# 05-USB-UART.net
KiCad netlist of a schematic drawn in Altium Designer
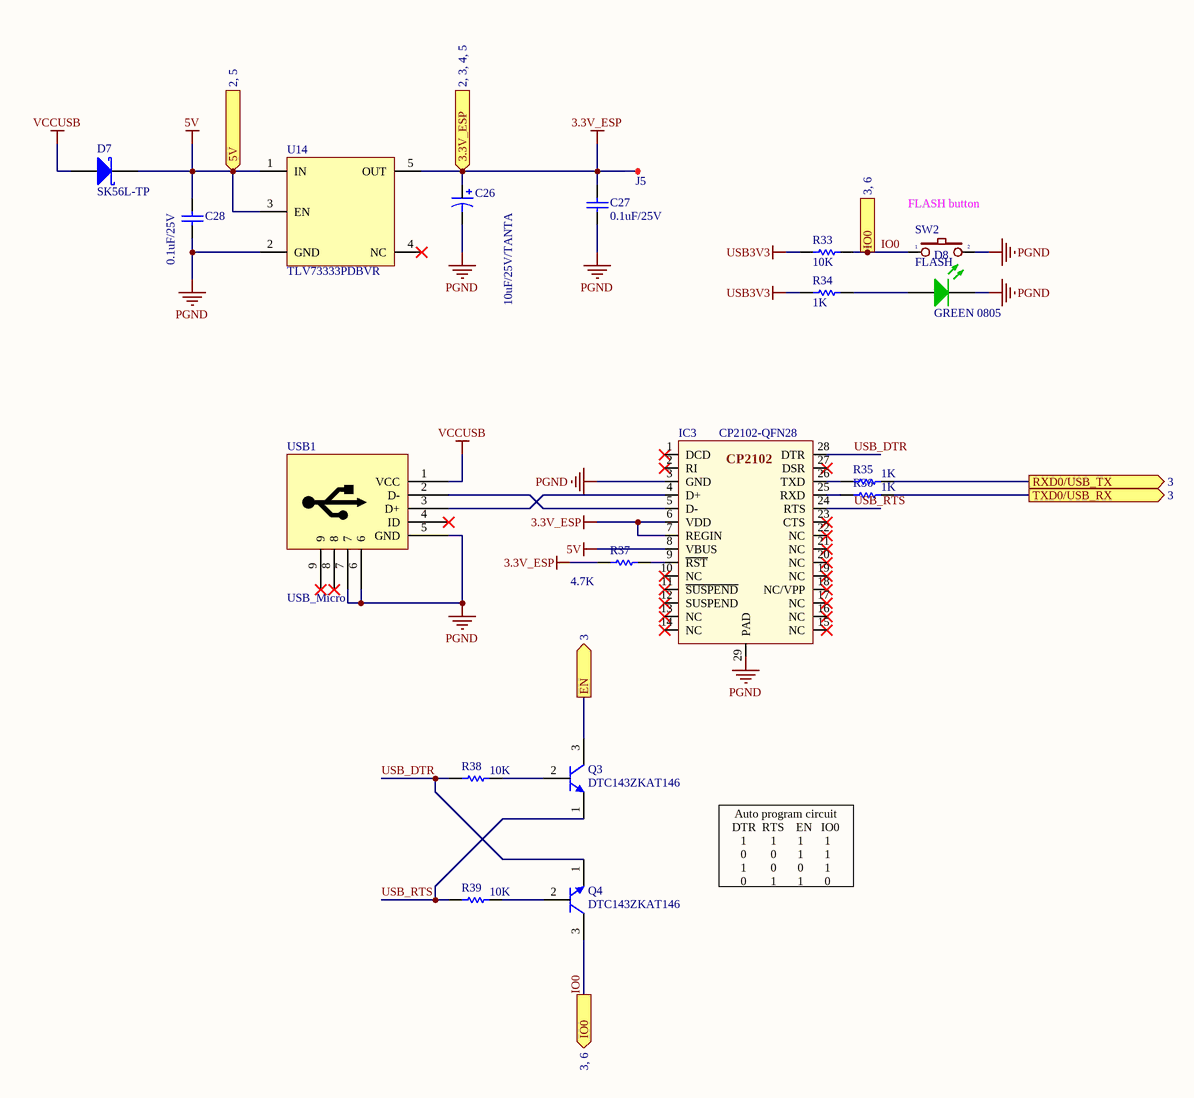
[diagram p0: 05-USB-UART.SchDoc]

(export (version "E")
  (design (tool "Eeschema 10.0.6"))
  (components
    (comp (ref "C26")
      (value "10uF/25V/TANTA")
      (footprint "CAP TANT CASE B SMD")
      (description "10µF Molded Tantalum Capacitors 25V 1411 (3528 Metric) 3 Ohm")
      (fields (field (name "MANUFACTURER") "KEMET"))
      (libsource (lib "GSHT_181013") (part "TAJB106M025RNJ"))
    )
    (comp (ref "C27")
      (value "0.1uF/25V")
      (footprint "CAP_CERA_C2012(CC0805INCH)")
      (description "0.1µF ±10% 25V Ceramic Capacitor X7R 0805 (2012 Metric)")
      (fields (field (name "MANUFACTURER") "KEMET"))
      (libsource (lib "GSHT_181013") (part "0.1uF/50V/C0603/10%"))
    )
    (comp (ref "C28")
      (value "0.1uF/25V")
      (footprint "CAP_CERA_C2012(CC0805INCH)")
      (description "0.1µF ±10% 25V Ceramic Capacitor X7R 0805 (2012 Metric)")
      (libsource (lib "GSHT_181013") (part "0.1uF/50V/C0603/10%"))
    )
    (comp (ref "D7")
      (value "SK56L-TP")
      (footprint "30# SK56L-TPMSCT-ND")
      (description "DIODE SCHOTTKY 60V 5A DO214AB")
      (libsource (lib "GSHT_181013") (part "30# SK56L-TP"))
    )
    (comp (ref "D8")
      (value "GREEN 0805")
      (footprint "Led 0805G")
      (description "Green 571nm LED Indication - Discrete 2V 0805 (2012 Metric)")
      (libsource (lib "GSHT_181013") (part "LED GREEN 0603"))
    )
    (comp (ref "IC3")
      (value "CP2102-QFN28")
      (footprint "CP2102-QFN28")
      (description "USB Bridge, USB to UART USB 2.0 UART Interface 28-QFN (5x5)")
      (libsource (lib "lpson") (part "CP2102"))
    )
    (comp (ref "J5")
      (value "TEST POINT")
      (footprint "TEST POINT 1mm")
      (description "TPoint")
      (libsource (lib "GSHT_181013") (part "PAD 1mm"))
    )
    (comp (ref "Q3")
      (value "DTC143ZKAT146")
      (footprint "6# DTC143ZKAT146-E")
      (description "Pre-Biased Bipolar Transistor (BJT) NPN - Pre-Biased 50V 100mA 250MHz 200mW Surface Mount SMT3")
      (libsource (lib "GSHT_181013") (part "6#DTC143ZKAT146"))
    )
    (comp (ref "Q4")
      (value "DTC143ZKAT146")
      (footprint "6# DTC143ZKAT146-E")
      (description "Pre-Biased Bipolar Transistor (BJT) NPN - Pre-Biased 50V 100mA 250MHz 200mW Surface Mount SMT3")
      (libsource (lib "GSHT_181013") (part "6#DTC143ZKAT146"))
    )
    (comp (ref "R33")
      (value "10K")
      (footprint "Res 0805 SMD")
      (description "10 kOhms ±1% 0.125W, 1/8W Chip Resistor 0805 (2012 Metric) Thick Film")
      (libsource (lib "GSHT_181013") (part "200K/R0603/1%"))
    )
    (comp (ref "R34")
      (value "1K")
      (footprint "Res 0805 SMD")
      (description "1 kOhms ±1% 0.125W, 1/8W Chip Resistor 0805 (2012 Metric) Automotive AEC-Q200 Thick Film")
      (libsource (lib "GSHT_181013") (part "200K/R0603/1%"))
    )
    (comp (ref "R35")
      (value "1K")
      (footprint "Res 0805 SMD")
      (description "1 kOhms ±1% 0.125W, 1/8W Chip Resistor 0805 (2012 Metric) Automotive AEC-Q200 Thick Film")
      (libsource (lib "GSHT_181013") (part "34.8K/R0805/1%"))
    )
    (comp (ref "R36")
      (value "1K")
      (footprint "Res 0805 SMD")
      (description "1 kOhms ±1% 0.125W, 1/8W Chip Resistor 0805 (2012 Metric) Automotive AEC-Q200 Thick Film")
      (libsource (lib "GSHT_181013") (part "34.8K/R0805/1%"))
    )
    (comp (ref "R37")
      (value "4.7K")
      (footprint "Res 0805 SMD")
      (description "4.7 kOhms ±1% 0.125W, 1/8W Chip Resistor 0805 (2012 Metric) Thick Film")
      (libsource (lib "GSHT_181013") (part "34.8K/R0805/1%"))
    )
    (comp (ref "R38")
      (value "10K")
      (footprint "Res 0805 SMD")
      (description "10 kOhms ±1% 0.125W, 1/8W Chip Resistor 0805 (2012 Metric) Thick Film")
      (libsource (lib "GSHT_181013") (part "34.8K/R0805/1%"))
    )
    (comp (ref "R39")
      (value "10K")
      (footprint "Res 0805 SMD")
      (description "10 kOhms ±1% 0.125W, 1/8W Chip Resistor 0805 (2012 Metric) Thick Film")
      (libsource (lib "GSHT_181013") (part "34.8K/R0805/1%"))
    )
    (comp (ref "SW2")
      (value "FLASH")
      (footprint "Button 3x4mm")
      (description "SWITCH TACTILE SPST-NO 0.05A 12V")
      (libsource (lib "lpson") (part "SW2"))
    )
    (comp (ref "U14")
      (value "TLV73333PDBVR")
      (footprint "20# TLV73333PDBVR")
      (description "Linear Voltage Regulator IC Positive Fixed 1 Output 3.3V 300mA SOT-23-5")
      (libsource (lib "GSHT_181013") (part "20#TLV73333PDBVR"))
    )
    (comp (ref "USB1")
      (value "USB_Micro")
      (footprint "USB_MICRO_B - Digikey")
      (description "USB - micro B USB 2.0 Receptacle Connector 5 Position Surface Mount, Right Angle; Through Hole")
      (libsource (lib "lpson") (part "USB_MINI"))
    )
  )
  (nets
    (net (code "1") (name "/EN") (class "Default")
      (node (ref "Q3") (pin "3") (pinfunction "C_3") (pintype "passive"))
    )
    (net (code "2") (name "/IO0") (class "Default")
      (node (ref "Q4") (pin "3") (pinfunction "C_3") (pintype "passive"))
      (node (ref "R33") (pin "2") (pinfunction "2_2") (pintype "passive"))
      (node (ref "SW2") (pin "1") (pinfunction "1_1") (pintype "passive"))
    )
    (net (code "3") (name "/RXD0{slash}USB_TX") (class "Default")
      (node (ref "R35") (pin "1") (pinfunction "1_1") (pintype "passive"))
    )
    (net (code "4") (name "/TXD0{slash}USB_RX") (class "Default")
      (node (ref "R36") (pin "1") (pinfunction "1_1") (pintype "passive"))
    )
    (net (code "5") (name "/USB_DTR") (class "Default")
      (node (ref "IC3") (pin "28") (pinfunction "DTR_28") (pintype "passive"))
      (node (ref "Q4") (pin "1") (pinfunction "E_1") (pintype "passive"))
      (node (ref "R38") (pin "2") (pinfunction "2_2") (pintype "passive"))
    )
    (net (code "6") (name "/USB_RTS") (class "Default")
      (node (ref "IC3") (pin "24") (pinfunction "RTS_24") (pintype "passive"))
      (node (ref "Q3") (pin "1") (pinfunction "E_1") (pintype "passive"))
      (node (ref "R39") (pin "2") (pinfunction "2_2") (pintype "passive"))
    )
    (net (code "7") (name "3.3V_ESP") (class "Default")
      (node (ref "C26") (pin "1") (pinfunction "1_1") (pintype "passive"))
      (node (ref "C27") (pin "2") (pinfunction "2_2") (pintype "passive"))
      (node (ref "IC3") (pin "6") (pinfunction "VDD_6") (pintype "passive"))
      (node (ref "IC3") (pin "7") (pinfunction "REGIN_7") (pintype "passive"))
      (node (ref "J5") (pin "1") (pinfunction "TP_1") (pintype "passive"))
      (node (ref "R37") (pin "1") (pinfunction "1_1") (pintype "passive"))
      (node (ref "U14") (pin "5") (pinfunction "OUT_5") (pintype "passive"))
    )
    (net (code "8") (name "5V") (class "Default")
      (node (ref "C28") (pin "2") (pinfunction "2_2") (pintype "passive"))
      (node (ref "D7") (pin "2") (pinfunction "K_2") (pintype "passive"))
      (node (ref "IC3") (pin "8") (pinfunction "VBUS_8") (pintype "passive"))
      (node (ref "U14") (pin "1") (pinfunction "IN_1") (pintype "passive"))
      (node (ref "U14") (pin "3") (pinfunction "EN_3") (pintype "passive"))
    )
    (net (code "9") (name "Net-(D8-A)") (class "Default")
      (node (ref "D8") (pin "1") (pinfunction "A_1") (pintype "passive"))
      (node (ref "R34") (pin "2") (pinfunction "2_2") (pintype "passive"))
    )
    (net (code "10") (name "Net-(IC3-D+)") (class "Default")
      (node (ref "IC3") (pin "4") (pinfunction "D+_4") (pintype "passive"))
      (node (ref "USB1") (pin "3") (pinfunction "D+_3") (pintype "passive"))
    )
    (net (code "11") (name "Net-(IC3-D-)") (class "Default")
      (node (ref "IC3") (pin "5") (pinfunction "D-_5") (pintype "passive"))
      (node (ref "USB1") (pin "2") (pinfunction "D-_2") (pintype "passive"))
    )
    (net (code "12") (name "Net-(IC3-RXD)") (class "Default")
      (node (ref "IC3") (pin "25") (pinfunction "RXD_25") (pintype "passive"))
      (node (ref "R36") (pin "2") (pinfunction "2_2") (pintype "passive"))
    )
    (net (code "13") (name "Net-(IC3-TXD)") (class "Default")
      (node (ref "IC3") (pin "26") (pinfunction "TXD_26") (pintype "passive"))
      (node (ref "R35") (pin "2") (pinfunction "2_2") (pintype "passive"))
    )
    (net (code "14") (name "Net-(IC3-~{RST})") (class "Default")
      (node (ref "IC3") (pin "9") (pinfunction "~{RST}_9") (pintype "passive"))
      (node (ref "R37") (pin "2") (pinfunction "2_2") (pintype "passive"))
    )
    (net (code "15") (name "Net-(Q3-B)") (class "Default")
      (node (ref "Q3") (pin "2") (pinfunction "B_2") (pintype "passive"))
      (node (ref "R38") (pin "1") (pinfunction "1_1") (pintype "passive"))
    )
    (net (code "16") (name "Net-(Q4-B)") (class "Default")
      (node (ref "Q4") (pin "2") (pinfunction "B_2") (pintype "passive"))
      (node (ref "R39") (pin "1") (pinfunction "1_1") (pintype "passive"))
    )
    (net (code "17") (name "PGND") (class "Default")
      (node (ref "C26") (pin "2") (pinfunction "2_2") (pintype "passive"))
      (node (ref "C27") (pin "1") (pinfunction "1_1") (pintype "passive"))
      (node (ref "C28") (pin "1") (pinfunction "1_1") (pintype "passive"))
      (node (ref "D8") (pin "2") (pinfunction "K_2") (pintype "passive"))
      (node (ref "IC3") (pin "29") (pinfunction "PAD_29") (pintype "passive"))
      (node (ref "IC3") (pin "3") (pinfunction "GND_3") (pintype "passive"))
      (node (ref "SW2") (pin "2") (pinfunction "2_2") (pintype "passive"))
      (node (ref "U14") (pin "2") (pinfunction "GND_2") (pintype "passive"))
      (node (ref "USB1") (pin "5") (pinfunction "GND_5") (pintype "passive"))
      (node (ref "USB1") (pin "6") (pinfunction "6_6") (pintype "passive"))
      (node (ref "USB1") (pin "7") (pinfunction "7_7") (pintype "passive"))
    )
    (net (code "18") (name "USB3V3") (class "Default")
      (node (ref "R33") (pin "1") (pinfunction "1_1") (pintype "passive"))
      (node (ref "R34") (pin "1") (pinfunction "1_1") (pintype "passive"))
    )
    (net (code "19") (name "VCCUSB") (class "Default")
      (node (ref "D7") (pin "1") (pinfunction "A_1") (pintype "passive"))
      (node (ref "USB1") (pin "1") (pinfunction "VCC_1") (pintype "passive"))
    )
    (net (code "20") (name "unconnected-(IC3-CTS-Pad23)") (class "Default")
      (node (ref "IC3") (pin "23") (pinfunction "CTS_23") (pintype "passive+no_connect"))
    )
    (net (code "21") (name "unconnected-(IC3-DCD-Pad1)") (class "Default")
      (node (ref "IC3") (pin "1") (pinfunction "DCD_1") (pintype "passive+no_connect"))
    )
    (net (code "22") (name "unconnected-(IC3-DSR-Pad27)") (class "Default")
      (node (ref "IC3") (pin "27") (pinfunction "DSR_27") (pintype "passive+no_connect"))
    )
    (net (code "23") (name "unconnected-(IC3-NC-Pad10)") (class "Default")
      (node (ref "IC3") (pin "10") (pinfunction "NC_10") (pintype "passive+no_connect"))
    )
    (net (code "24") (name "unconnected-(IC3-NC-Pad13)") (class "Default")
      (node (ref "IC3") (pin "13") (pinfunction "NC_13") (pintype "passive+no_connect"))
    )
    (net (code "25") (name "unconnected-(IC3-NC-Pad14)") (class "Default")
      (node (ref "IC3") (pin "14") (pinfunction "NC_14") (pintype "passive+no_connect"))
    )
    (net (code "26") (name "unconnected-(IC3-NC-Pad15)") (class "Default")
      (node (ref "IC3") (pin "15") (pinfunction "NC_15") (pintype "passive+no_connect"))
    )
    (net (code "27") (name "unconnected-(IC3-NC-Pad16)") (class "Default")
      (node (ref "IC3") (pin "16") (pinfunction "NC_16") (pintype "passive+no_connect"))
    )
    (net (code "28") (name "unconnected-(IC3-NC-Pad17)") (class "Default")
      (node (ref "IC3") (pin "17") (pinfunction "NC_17") (pintype "passive+no_connect"))
    )
    (net (code "29") (name "unconnected-(IC3-NC-Pad19)") (class "Default")
      (node (ref "IC3") (pin "19") (pinfunction "NC_19") (pintype "passive+no_connect"))
    )
    (net (code "30") (name "unconnected-(IC3-NC-Pad20)") (class "Default")
      (node (ref "IC3") (pin "20") (pinfunction "NC_20") (pintype "passive+no_connect"))
    )
    (net (code "31") (name "unconnected-(IC3-NC-Pad21)") (class "Default")
      (node (ref "IC3") (pin "21") (pinfunction "NC_21") (pintype "passive+no_connect"))
    )
    (net (code "32") (name "unconnected-(IC3-NC-Pad22)") (class "Default")
      (node (ref "IC3") (pin "22") (pinfunction "NC_22") (pintype "passive+no_connect"))
    )
    (net (code "33") (name "unconnected-(IC3-NC{slash}VPP-Pad18)") (class "Default")
      (node (ref "IC3") (pin "18") (pinfunction "NC/VPP_18") (pintype "passive+no_connect"))
    )
    (net (code "34") (name "unconnected-(IC3-RI-Pad2)") (class "Default")
      (node (ref "IC3") (pin "2") (pinfunction "RI_2") (pintype "passive+no_connect"))
    )
    (net (code "35") (name "unconnected-(IC3-SUSPEND-Pad12)") (class "Default")
      (node (ref "IC3") (pin "12") (pinfunction "SUSPEND_12") (pintype "passive+no_connect"))
    )
    (net (code "36") (name "unconnected-(IC3-~{SUSPEND}-Pad11)") (class "Default")
      (node (ref "IC3") (pin "11") (pinfunction "~{SUSPEND}_11") (pintype "passive+no_connect"))
    )
    (net (code "37") (name "unconnected-(U14-NC-Pad4)") (class "Default")
      (node (ref "U14") (pin "4") (pinfunction "NC_4") (pintype "passive+no_connect"))
    )
    (net (code "38") (name "unconnected-(USB1-ID-Pad4)") (class "Default")
      (node (ref "USB1") (pin "4") (pinfunction "ID_4") (pintype "passive+no_connect"))
    )
    (net (code "39") (name "unconnected-(USB1-Pad8)") (class "Default")
      (node (ref "USB1") (pin "8") (pinfunction "8_8") (pintype "passive+no_connect"))
    )
    (net (code "40") (name "unconnected-(USB1-Pad9)") (class "Default")
      (node (ref "USB1") (pin "9") (pinfunction "9_9") (pintype "passive+no_connect"))
    )
  )
)
